# Domino_Single_USB_No_Teardrop.net
KiCad netlist of a schematic drawn in EAGLE
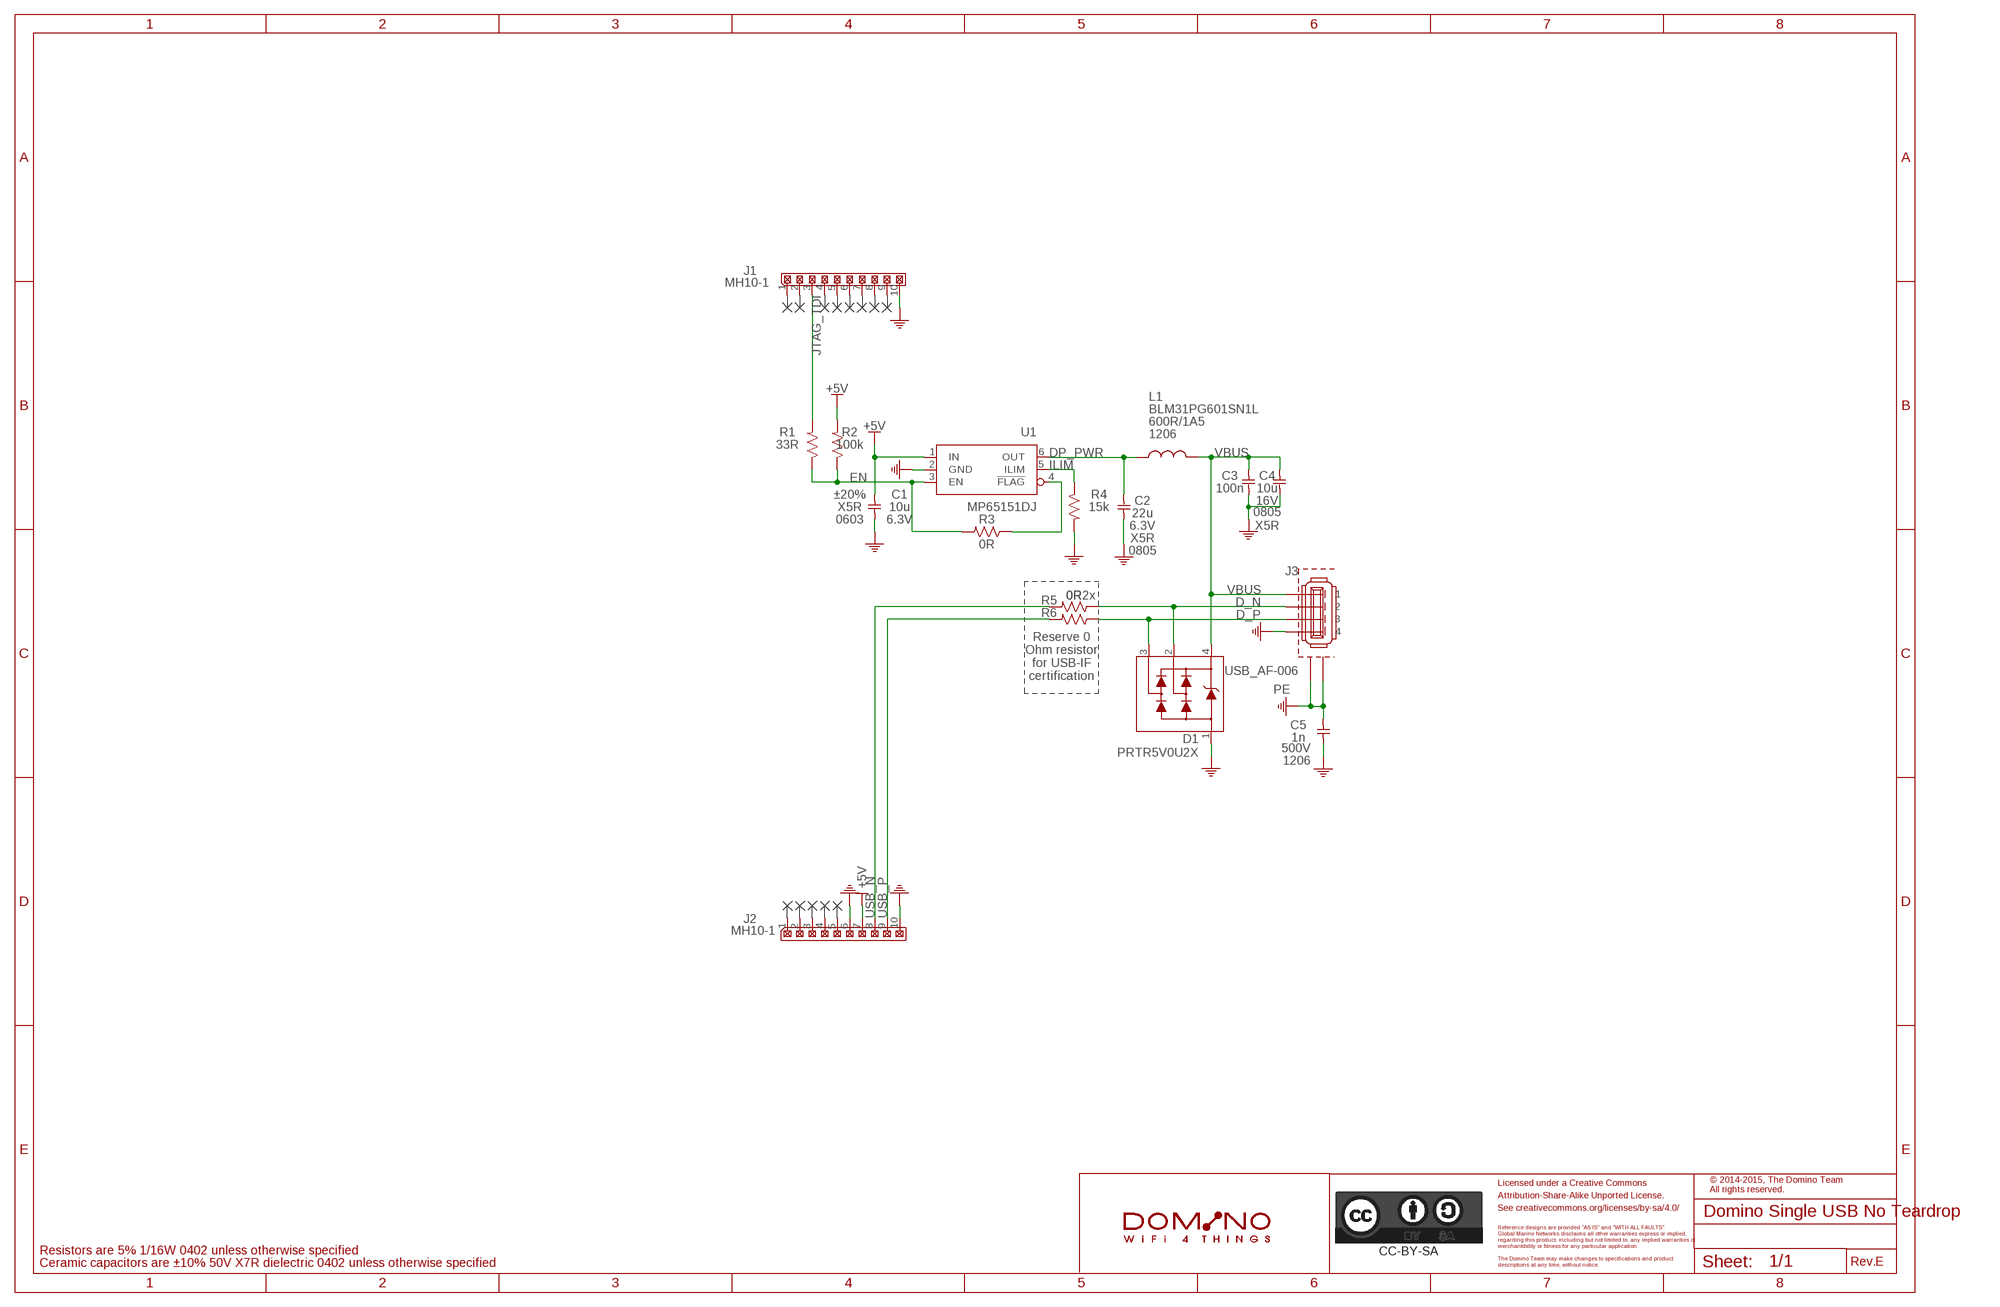
[diagram p0: schematic, sheet 1]

(export (version "E")
  (design (tool "Eeschema 10.0.6"))
  (components
    (comp (ref "C1")
      (value "10u")
      (footprint "eagle-import:C0603")
      (fields
        (field (name "SIZE") "0603")
        (field (name "PARTNO") "C0603_10u_X5R_20%_CER_6V3")
        (field (name "TC") "X5R")
        (field (name "TOL") "±20%")
        (field (name "VOLT") "6.3V")
      )
      (libsource (lib "eagle-import") (part "CAP_0603"))
    )
    (comp (ref "C2")
      (value "22u")
      (footprint "eagle-import:C0805")
      (fields
        (field (name "SIZE") "0805")
        (field (name "PARTNO") "C0805_22u_X5R_20%_CER_6V3")
        (field (name "TC") "X5R")
        (field (name "VOLT") "6.3V")
      )
      (libsource (lib "eagle-import") (part "CAP_0805"))
    )
    (comp (ref "C3")
      (value "100n")
      (footprint "eagle-import:C0402")
      (fields (field (name "PARTNO") "C0402_100n_X7R_10%_CER_50V"))
      (libsource (lib "eagle-import") (part "CAP_0402"))
    )
    (comp (ref "C4")
      (value "10u")
      (footprint "eagle-import:C0805")
      (fields
        (field (name "SIZE") "0805")
        (field (name "PARTNO") "C0805_10u_X5R_10%_CER_16V")
        (field (name "TC") "X5R")
        (field (name "VOLT") "16V")
      )
      (libsource (lib "eagle-import") (part "CAP_0805"))
    )
    (comp (ref "C5")
      (value "1n")
      (footprint "eagle-import:C1206")
      (fields
        (field (name "SIZE") "1206")
        (field (name "PARTNO") "C1206_1n_X7R_10%_CER_500V")
        (field (name "VOLT") "500V")
      )
      (libsource (lib "eagle-import") (part "CAP_1206"))
    )
    (comp (ref "CC-BY-SA1")
      (value "CC-BY-SA_LOGO")
      (footprint "eagle-import:CC-BY-SA_LOGO")
      (libsource (lib "eagle-import") (part "CC-BY-SA_LOGO"))
    )
    (comp (ref "D1")
      (value "PRTR5V0U2X")
      (footprint "eagle-import:SOT143B")
      (libsource (lib "eagle-import") (part "PRTR5V0U2X"))
    )
    (comp (ref "J1")
      (value "MH10-1")
      (footprint "eagle-import:MH10-1-0.1")
      (fields (field (name "PARTNO") "MH10-1-0.1"))
      (libsource (lib "eagle-import") (part "MH10-1"))
    )
    (comp (ref "J2")
      (value "MH10-1")
      (footprint "eagle-import:MH10-1-0.1")
      (fields (field (name "PARTNO") "MH10-1-0.1"))
      (libsource (lib "eagle-import") (part "MH10-1"))
    )
    (comp (ref "J3")
      (value "USB_AF-006")
      (footprint "eagle-import:USB_AF-006")
      (libsource (lib "eagle-import") (part "USB_AF-006"))
    )
    (comp (ref "L1")
      (value "BLM31PG601SN1L")
      (footprint "eagle-import:FB1206")
      (fields (field (name "SIZE") "1206") (field (name "OPT") "600R/1A5"))
      (libsource (lib "eagle-import") (part "FB_1206"))
    )
    (comp (ref "R1")
      (value "33R")
      (footprint "eagle-import:R0402")
      (fields (field (name "PARTNO") "R0402_33R_5%_62.5mW"))
      (libsource (lib "eagle-import") (part "RES_0402"))
    )
    (comp (ref "R2")
      (value "100k")
      (footprint "eagle-import:R0402")
      (fields (field (name "PARTNO") "R0402_100k_5%_62.5mW"))
      (libsource (lib "eagle-import") (part "RES_0402"))
    )
    (comp (ref "R3")
      (value "0R")
      (footprint "eagle-import:R0402")
      (fields (field (name "PARTNO") "R0402_0R_5%_62.5mW"))
      (libsource (lib "eagle-import") (part "RES_0402"))
    )
    (comp (ref "R4")
      (value "15k")
      (footprint "eagle-import:R0402")
      (fields (field (name "PARTNO") "R0402_15k_5%_62.5mW"))
      (libsource (lib "eagle-import") (part "RES_0402"))
    )
    (comp (ref "R5")
      (value "0R")
      (footprint "eagle-import:R0402")
      (fields (field (name "PARTNO") "R0402_0R_5%_62.5mW"))
      (libsource (lib "eagle-import") (part "RES_0402"))
    )
    (comp (ref "R6")
      (value "0R")
      (footprint "eagle-import:R0402")
      (fields (field (name "PARTNO") "R0402_0R_5%_62.5mW"))
      (libsource (lib "eagle-import") (part "RES_0402"))
    )
    (comp (ref "S1")
      (value "DOMINO_LOGO")
      (footprint "eagle-import:DOMINO_LOGO")
      (libsource (lib "eagle-import") (part "DOMINO_LOGO"))
    )
    (comp (ref "U1")
      (value "MP65151DJ")
      (footprint "eagle-import:SOT23-6")
      (libsource (lib "eagle-import") (part "MP65151DJ"))
    )
  )
  (nets
    (net (code "1") (name "+5V") (class "Default")
      (node (ref "C1") (pin "1") (pinfunction "1_1") (pintype "passive"))
      (node (ref "J2") (pin "7") (pinfunction "7_7") (pintype "passive"))
      (node (ref "R2") (pin "2") (pinfunction "2_2") (pintype "passive"))
      (node (ref "U1") (pin "1") (pinfunction "IN_1") (pintype "power_in"))
    )
    (net (code "2") (name "/DP_PWR") (class "Default")
      (node (ref "C2") (pin "1") (pinfunction "1_1") (pintype "passive"))
      (node (ref "L1") (pin "1") (pinfunction "1_1") (pintype "passive"))
      (node (ref "U1") (pin "6") (pinfunction "OUT_6") (pintype "power_in"))
    )
    (net (code "3") (name "/D_N") (class "Default")
      (node (ref "D1") (pin "2") (pinfunction "P$2_2") (pintype "passive"))
      (node (ref "J3") (pin "2") (pinfunction "2_2") (pintype "passive"))
      (node (ref "R5") (pin "1") (pinfunction "1_1") (pintype "passive"))
    )
    (net (code "4") (name "/D_P") (class "Default")
      (node (ref "D1") (pin "3") (pinfunction "P$3_3") (pintype "passive"))
      (node (ref "J3") (pin "3") (pinfunction "3_3") (pintype "passive"))
      (node (ref "R6") (pin "1") (pinfunction "1_1") (pintype "passive"))
    )
    (net (code "5") (name "/EN") (class "Default")
      (node (ref "R1") (pin "1") (pinfunction "1_1") (pintype "passive"))
      (node (ref "R2") (pin "1") (pinfunction "1_1") (pintype "passive"))
      (node (ref "R3") (pin "2") (pinfunction "2_2") (pintype "passive"))
      (node (ref "U1") (pin "3") (pinfunction "EN_3") (pintype "input"))
    )
    (net (code "6") (name "/ILIM") (class "Default")
      (node (ref "R4") (pin "1") (pinfunction "1_1") (pintype "passive"))
      (node (ref "U1") (pin "5") (pinfunction "ILIM_5") (pintype "passive"))
    )
    (net (code "7") (name "/JTAG_TDI") (class "Default")
      (node (ref "J1") (pin "3") (pinfunction "3_3") (pintype "passive"))
      (node (ref "R1") (pin "2") (pinfunction "2_2") (pintype "passive"))
    )
    (net (code "8") (name "/USB_N") (class "Default")
      (node (ref "J2") (pin "8") (pinfunction "8_8") (pintype "passive"))
      (node (ref "R5") (pin "2") (pinfunction "2_2") (pintype "passive"))
    )
    (net (code "9") (name "/USB_P") (class "Default")
      (node (ref "J2") (pin "9") (pinfunction "9_9") (pintype "passive"))
      (node (ref "R6") (pin "2") (pinfunction "2_2") (pintype "passive"))
    )
    (net (code "10") (name "/VBUS") (class "Default")
      (node (ref "C3") (pin "1") (pinfunction "1_1") (pintype "passive"))
      (node (ref "C4") (pin "1") (pinfunction "1_1") (pintype "passive"))
      (node (ref "D1") (pin "4") (pinfunction "P$4_4") (pintype "passive"))
      (node (ref "J3") (pin "1") (pinfunction "1_1") (pintype "passive"))
      (node (ref "L1") (pin "2") (pinfunction "2_2") (pintype "passive"))
    )
    (net (code "11") (name "GND") (class "Default")
      (node (ref "C1") (pin "2") (pinfunction "2_2") (pintype "passive"))
      (node (ref "C2") (pin "2") (pinfunction "2_2") (pintype "passive"))
      (node (ref "C3") (pin "2") (pinfunction "2_2") (pintype "passive"))
      (node (ref "C4") (pin "2") (pinfunction "2_2") (pintype "passive"))
      (node (ref "C5") (pin "2") (pinfunction "2_2") (pintype "passive"))
      (node (ref "D1") (pin "1") (pinfunction "P$1_1") (pintype "passive"))
      (node (ref "J1") (pin "10") (pinfunction "10_10") (pintype "passive"))
      (node (ref "J2") (pin "10") (pinfunction "10_10") (pintype "passive"))
      (node (ref "J2") (pin "6") (pinfunction "6_6") (pintype "passive"))
      (node (ref "J3") (pin "4") (pinfunction "4_4") (pintype "passive"))
      (node (ref "R4") (pin "2") (pinfunction "2_2") (pintype "passive"))
      (node (ref "U1") (pin "2") (pinfunction "GND_2") (pintype "power_in"))
    )
    (net (code "12") (name "Net-(U1-~{FLAG})") (class "Default")
      (node (ref "R3") (pin "1") (pinfunction "1_1") (pintype "passive"))
      (node (ref "U1") (pin "4") (pinfunction "~{FLAG}_4") (pintype "open_collector"))
    )
    (net (code "13") (name "PE") (class "Default")
      (node (ref "C5") (pin "1") (pinfunction "1_1") (pintype "passive"))
      (node (ref "J3") (pin "S$1") (pinfunction "G_S$1") (pintype "passive"))
      (node (ref "J3") (pin "S$2") (pinfunction "G_S$2") (pintype "passive"))
    )
    (net (code "14") (name "unconnected-(J1-Pad1)") (class "Default")
      (node (ref "J1") (pin "1") (pinfunction "1_1") (pintype "passive"))
    )
    (net (code "15") (name "unconnected-(J1-Pad2)") (class "Default")
      (node (ref "J1") (pin "2") (pinfunction "2_2") (pintype "passive"))
    )
    (net (code "16") (name "unconnected-(J1-Pad4)") (class "Default")
      (node (ref "J1") (pin "4") (pinfunction "4_4") (pintype "passive"))
    )
    (net (code "17") (name "unconnected-(J1-Pad5)") (class "Default")
      (node (ref "J1") (pin "5") (pinfunction "5_5") (pintype "passive"))
    )
    (net (code "18") (name "unconnected-(J1-Pad6)") (class "Default")
      (node (ref "J1") (pin "6") (pinfunction "6_6") (pintype "passive"))
    )
    (net (code "19") (name "unconnected-(J1-Pad7)") (class "Default")
      (node (ref "J1") (pin "7") (pinfunction "7_7") (pintype "passive"))
    )
    (net (code "20") (name "unconnected-(J1-Pad8)") (class "Default")
      (node (ref "J1") (pin "8") (pinfunction "8_8") (pintype "passive"))
    )
    (net (code "21") (name "unconnected-(J1-Pad9)") (class "Default")
      (node (ref "J1") (pin "9") (pinfunction "9_9") (pintype "passive"))
    )
    (net (code "22") (name "unconnected-(J2-Pad1)") (class "Default")
      (node (ref "J2") (pin "1") (pinfunction "1_1") (pintype "passive"))
    )
    (net (code "23") (name "unconnected-(J2-Pad2)") (class "Default")
      (node (ref "J2") (pin "2") (pinfunction "2_2") (pintype "passive"))
    )
    (net (code "24") (name "unconnected-(J2-Pad3)") (class "Default")
      (node (ref "J2") (pin "3") (pinfunction "3_3") (pintype "passive"))
    )
    (net (code "25") (name "unconnected-(J2-Pad4)") (class "Default")
      (node (ref "J2") (pin "4") (pinfunction "4_4") (pintype "passive"))
    )
    (net (code "26") (name "unconnected-(J2-Pad5)") (class "Default")
      (node (ref "J2") (pin "5") (pinfunction "5_5") (pintype "passive"))
    )
  )
)
